# ECG_MCU_Core.net
KiCad netlist of a schematic drawn in Altium Designer
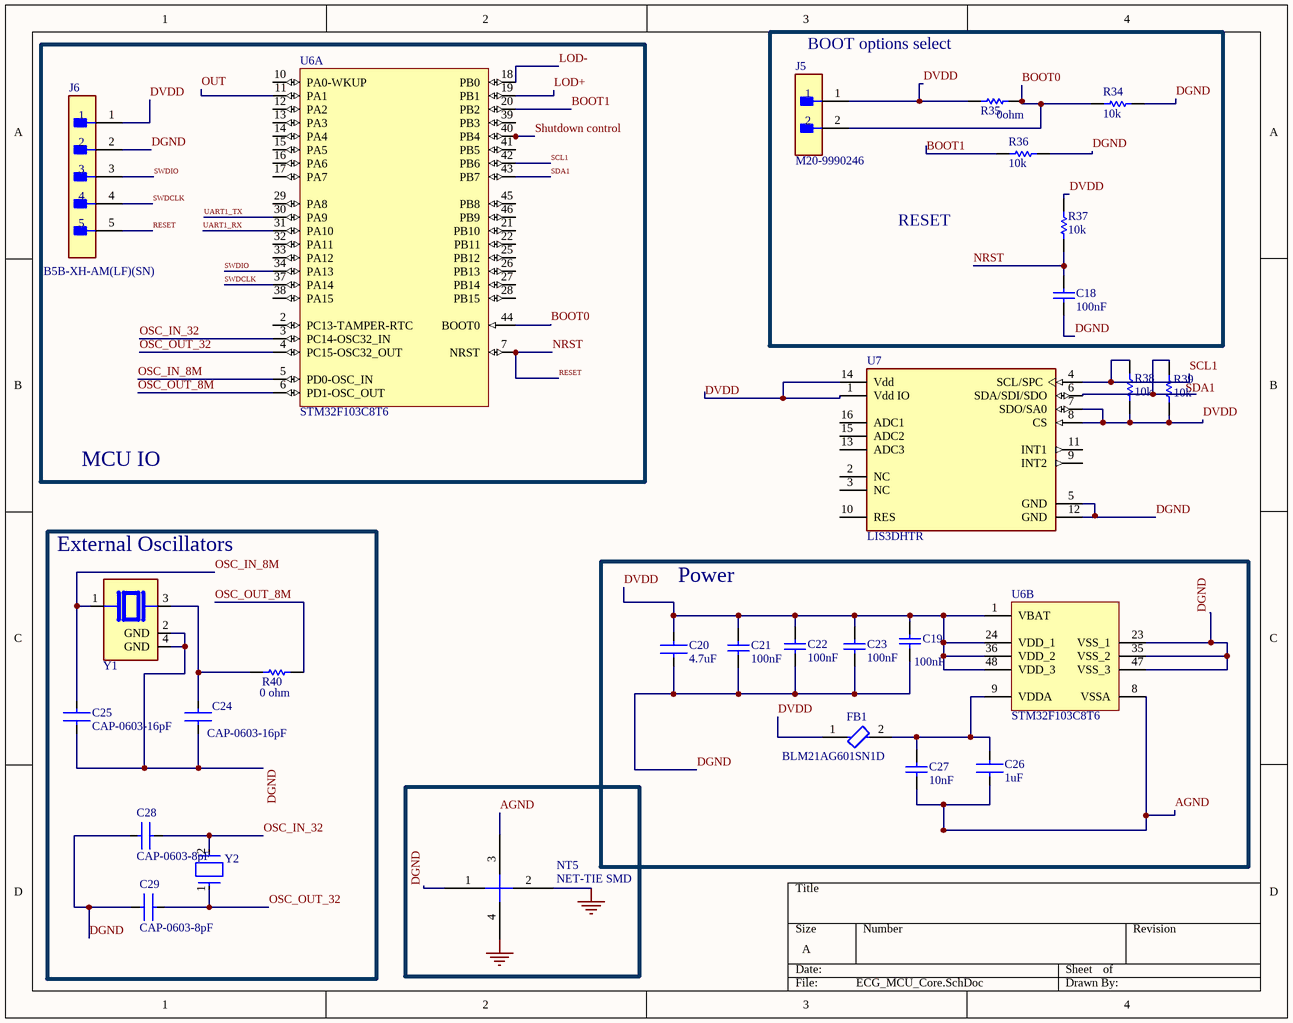
[diagram p0: ECG_MCU_Core.SchDoc]

(export (version "E")
  (design (tool "Eeschema 10.0.6"))
  (components
    (comp (ref "C18")
      (value "100nF")
      (footprint "CAP-0603-IPC_B")
      (fields
        (field (name "MANUFACTURER") "AVX Interconnect / Elco")
        (field (name "PART NUMBER") "0603ZC103MAT2A")
      )
      (libsource (lib "ecg_device_components") (part "1nF CAP-0603-IPC-B_1"))
    )
    (comp (ref "C19")
      (value "100nF")
      (footprint "CAP-0603-IPC_B")
      (fields
        (field (name "MANUFACTURER") "AVX Interconnect / Elco")
        (field (name "PART NUMBER") "0603ZC103MAT2A")
      )
      (libsource (lib "ecg_device_components") (part "CAP-0603-IPC-B"))
    )
    (comp (ref "C20")
      (value "4.7uF")
      (footprint "CAP-0805-IPC_B")
      (libsource (lib "ecg_device_components") (part "4.7uF CAP-0805-IPC-B_1"))
    )
    (comp (ref "C21")
      (value "100nF")
      (footprint "CAP-0603-IPC_B")
      (fields
        (field (name "MANUFACTURER") "AVX Interconnect / Elco")
        (field (name "PART NUMBER") "0603ZC103MAT2A")
      )
      (libsource (lib "ecg_device_components") (part "CAP-0603-IPC-B"))
    )
    (comp (ref "C22")
      (value "100nF")
      (footprint "CAP-0603-IPC_B")
      (fields
        (field (name "MANUFACTURER") "AVX Interconnect / Elco")
        (field (name "PART NUMBER") "0603ZC103MAT2A")
      )
      (libsource (lib "ecg_device_components") (part "CAP-0603-IPC-B"))
    )
    (comp (ref "C23")
      (value "100nF")
      (footprint "CAP-0603-IPC_B")
      (fields
        (field (name "MANUFACTURER") "AVX Interconnect / Elco")
        (field (name "PART NUMBER") "0603ZC103MAT2A")
      )
      (libsource (lib "ecg_device_components") (part "CAP-0603-IPC-B"))
    )
    (comp (ref "C24")
      (value "CAP-0603-16pF")
      (footprint "FP-GCM188-0_1-IPC_A_murata")
      (description "Ceramic Capacitor for Automotive 16pF  ±5% 100VDC C0G 0603 Paper T/R")
      (fields (field (name "TOLERANCE") "5%"))
      (libsource (lib "ecg_device_components") (part "CAP-0603_16V- 16pf_murata"))
    )
    (comp (ref "C25")
      (value "CAP-0603-16pF")
      (footprint "FP-GCM188-0_1-IPC_A_murata")
      (description "Ceramic Capacitor for Automotive 16pF  ±5% 100VDC C0G 0603 Paper T/R")
      (fields (field (name "TOLERANCE") "5%"))
      (libsource (lib "ecg_device_components") (part "CAP-0603_16V- 16pf_murata"))
    )
    (comp (ref "C26")
      (value "1uF")
      (footprint "CAP-0805-IPC_B")
      (libsource (lib "ecg_device_components") (part "1uF CAP-0805-IPC-B_1"))
    )
    (comp (ref "C27")
      (value "10nF")
      (footprint "CAP-0603-IPC_B")
      (fields
        (field (name "MANUFACTURER") "AVX Interconnect / Elco")
        (field (name "PART NUMBER") "0603ZC103MAT2A")
      )
      (libsource (lib "ecg_device_components") (part "CAP-0603-IPC-B"))
    )
    (comp (ref "C28")
      (value "CAP-0603-8pF")
      (footprint "FP-GCM188-0_1-IPC_A_murata")
      (description "Ceramic Capacitor for Automotive 16pF  ±5% 100VDC C0G 0603 Paper T/R")
      (fields (field (name "TOLERANCE") "5%"))
      (libsource (lib "ecg_device_components") (part "CAP-0603_16V- 8pF_murata"))
    )
    (comp (ref "C29")
      (value "CAP-0603-8pF")
      (footprint "FP-GCM188-0_1-IPC_A_murata")
      (description "Ceramic Capacitor for Automotive 16pF  ±5% 100VDC C0G 0603 Paper T/R")
      (fields (field (name "TOLERANCE") "5%"))
      (libsource (lib "ecg_device_components") (part "CAP-0603_16V- 8pF_murata"))
    )
    (comp (ref "FB1")
      (value "BLM21AG601SN1D")
      (footprint "Ferrite bead")
      (description "Chip Ferrite Bead, 0805, 600Ω @ 100MHz, 0.2Ω, 25%, 700mA")
      (fields (field (name "TOLERANCE") "25%"))
      (libsource (lib "ecg_device_components") (part "CMP-0686-00639-3 Ferrite bead"))
    )
    (comp (ref "J5")
      (value "M20-9990246")
      (footprint "FP-M20-9990246-MFG")
      (description "CONN HEADER VERT 2POS 2.54MM")
      (fields
        (field (name "OCTOPART") "https://octopart.com/m20-9990246-harwin-2590635")
        (field (name "MANUFACTURER") "Harwin")
      )
      (libsource (lib "Altium Content Vault") (part "3bc925449376181038e59eaffc5286c"))
    )
    (comp (ref "J6")
      (value "B5B-XH-AM(LF)(SN)")
      (footprint "FP-B5B-XH-AM_LF_SN-MFG")
      (description "CONN HEADER VERT 5POS 2.5MM")
      (libsource (lib "Altium Content Vault") (part "bf93c07fd2649a848d0ec8585582aab"))
    )
    (comp (ref "NT5")
      (value "NET-TIE SMD")
      (footprint "NET TIE SMD")
      (libsource (lib "ecg_device_components") (part "NET-TIE SMD"))
    )
    (comp (ref "R34")
      (value "10k")
      (footprint "RES-0603-IPC_B")
      (fields (field (name "TOLERANCE") "0.5%"))
      (libsource (lib "ecg_device_components") (part "10k RES-0603-IPC-B_1_1"))
    )
    (comp (ref "R35")
      (value "0ohm")
      (footprint "RES-0603-IPC_B")
      (fields (field (name "TOLERANCE") "0.5%"))
      (libsource (lib "ecg_device_components") (part "1k RES-0603-IPC-B_1"))
    )
    (comp (ref "R36")
      (value "10k")
      (footprint "RES-0603-IPC_B")
      (fields (field (name "TOLERANCE") "0.5%"))
      (libsource (lib "ecg_device_components") (part "10k RES-0603-IPC-B_1_1"))
    )
    (comp (ref "R37")
      (value "10k")
      (footprint "RES-0603-IPC_B")
      (fields (field (name "TOLERANCE") "0.5%"))
      (libsource (lib "ecg_device_components") (part "10k RES-0603-IPC-B_1_1"))
    )
    (comp (ref "R38")
      (value "10k")
      (footprint "RES-0603-IPC_B")
      (fields (field (name "TOLERANCE") "0.5%"))
      (libsource (lib "ecg_device_components") (part "10k RES-0603-IPC-B_1_1"))
    )
    (comp (ref "R39")
      (value "10k")
      (footprint "RES-0603-IPC_B")
      (fields (field (name "TOLERANCE") "0.5%"))
      (libsource (lib "ecg_device_components") (part "10k RES-0603-IPC-B_1_1"))
    )
    (comp (ref "R40")
      (value "0 ohm")
      (footprint "RES-0603-IPC_B")
      (fields (field (name "TOLERANCE") "0.5%"))
      (libsource (lib "ecg_device_components") (part "RES-0603-IPC-B"))
    )
    (comp (ref "U6")
      (value "STM32F103C8T6")
      (footprint "STM-LQFP48_M")
      (description "MCU 32-bit STM32F1 ARM Cortex M3 RISC 64KB Flash 2.5V/3.3V 48-Pin LQFP Tray")
      (fields (field (name "MANUFACTURER") "STMicroelectronics"))
      (libsource (lib "ecg_device_components") (part "STM32F103C8T6"))
    )
    (comp (ref "U7")
      (value "LIS3DHTR")
      (footprint "FP-LGA-16-7983231-MFG")
      (description "ACCEL 2-16G I2C/SPI 16LGA")
      (libsource (lib "Altium Content Vault") (part "1e4772b22d749da4b53766bc623c8dd"))
    )
    (comp (ref "Y1")
      (value "ABM8AIG-8.000MHZ-1Z-T_1")
      (footprint "XTAL_ABM8AIG-8.000MHZ-1Z-T")
      (description "Crystal, Aec-Q200, 8Mhz, 3.2Mm X 2.5Mm Rohs Compliant: Yes ¦Abracon ABM8AIG-8.000MHZ-1Z-T")
      (fields (field (name "MF") "Abracon LLC") (field (name "MP") "ABM8AIG-8.000MHZ-1Z-T"))
      (libsource (lib "ecg_device_components") (part "ABM8AIG-8.000MHZ-1Z-T_1"))
    )
    (comp (ref "Y2")
      (value "ABS07-32.768KHZ-6-T")
      (footprint "FP-ABS07-MFG")
      (description "Crystal 32.768kHz ±20ppm (Tol) 6pF FUND 70kΩ 2-Pin CSMD T/R")
      (fields (field (name "TOLERANCE") "20ppm"))
      (libsource (lib "Altium Content Vault") (part "c23a69dc6c9e2f18f2079038eb95dd1"))
    )
  )
  (nets
    (net (code "1") (name "/AGND") (class "Default")
      (node (ref "C26") (pin "1") (pinfunction "1_1") (pintype "passive"))
      (node (ref "C27") (pin "1") (pinfunction "1_1") (pintype "passive"))
      (node (ref "NT5") (pin "3") (pinfunction "3_3") (pintype "passive"))
      (node (ref "U6") (pin "8") (pinfunction "VSSA_8") (pintype "power_in"))
    )
    (net (code "2") (name "/BOOT0") (class "Default")
      (node (ref "J5") (pin "2") (pinfunction "2_2") (pintype "passive"))
      (node (ref "R34") (pin "1") (pinfunction "1_1") (pintype "passive"))
      (node (ref "R35") (pin "2") (pinfunction "2_2") (pintype "passive"))
      (node (ref "U6") (pin "44") (pinfunction "BOOT0_44") (pintype "input"))
    )
    (net (code "3") (name "/BOOT1") (class "Default")
      (node (ref "R36") (pin "1") (pinfunction "1_1") (pintype "passive"))
      (node (ref "U6") (pin "20") (pinfunction "PB2_20") (pintype "bidirectional"))
    )
    (net (code "4") (name "/DGND") (class "Default")
      (node (ref "C18") (pin "1") (pinfunction "1_1") (pintype "passive"))
      (node (ref "C19") (pin "1") (pinfunction "1_1") (pintype "passive"))
      (node (ref "C20") (pin "2") (pinfunction "2_2") (pintype "passive"))
      (node (ref "C21") (pin "1") (pinfunction "1_1") (pintype "passive"))
      (node (ref "C22") (pin "1") (pinfunction "1_1") (pintype "passive"))
      (node (ref "C23") (pin "1") (pinfunction "1_1") (pintype "passive"))
      (node (ref "C24") (pin "1") (pinfunction "1_1") (pintype "passive"))
      (node (ref "C25") (pin "1") (pinfunction "1_1") (pintype "passive"))
      (node (ref "C28") (pin "2") (pinfunction "2_2") (pintype "passive"))
      (node (ref "C29") (pin "1") (pinfunction "1_1") (pintype "passive"))
      (node (ref "J6") (pin "2") (pinfunction "2_2") (pintype "passive"))
      (node (ref "NT5") (pin "1") (pinfunction "0_1") (pintype "passive"))
      (node (ref "R34") (pin "2") (pinfunction "2_2") (pintype "passive"))
      (node (ref "R36") (pin "2") (pinfunction "2_2") (pintype "passive"))
      (node (ref "U6") (pin "23") (pinfunction "VSS_1_23") (pintype "power_in"))
      (node (ref "U6") (pin "35") (pinfunction "VSS_2_35") (pintype "power_in"))
      (node (ref "U6") (pin "47") (pinfunction "VSS_3_47") (pintype "power_in"))
      (node (ref "U7") (pin "12") (pinfunction "GND_12") (pintype "power_in"))
      (node (ref "U7") (pin "5") (pinfunction "GND_5") (pintype "power_in"))
      (node (ref "Y1") (pin "2") (pinfunction "GND_2") (pintype "power_in"))
      (node (ref "Y1") (pin "4") (pinfunction "GND_4") (pintype "power_in"))
    )
    (net (code "5") (name "/DVDD") (class "Default")
      (node (ref "C19") (pin "2") (pinfunction "2_2") (pintype "passive"))
      (node (ref "C20") (pin "1") (pinfunction "1_1") (pintype "passive"))
      (node (ref "C21") (pin "2") (pinfunction "2_2") (pintype "passive"))
      (node (ref "C22") (pin "2") (pinfunction "2_2") (pintype "passive"))
      (node (ref "C23") (pin "2") (pinfunction "2_2") (pintype "passive"))
      (node (ref "FB1") (pin "1") (pinfunction "1_1") (pintype "passive"))
      (node (ref "J5") (pin "1") (pinfunction "1_1") (pintype "passive"))
      (node (ref "J6") (pin "1") (pinfunction "1_1") (pintype "passive"))
      (node (ref "R35") (pin "1") (pinfunction "1_1") (pintype "passive"))
      (node (ref "R37") (pin "2") (pinfunction "2_2") (pintype "passive"))
      (node (ref "R38") (pin "1") (pinfunction "1_1") (pintype "passive"))
      (node (ref "R39") (pin "1") (pinfunction "1_1") (pintype "passive"))
      (node (ref "U6") (pin "1") (pinfunction "VBAT_1") (pintype "power_in"))
      (node (ref "U6") (pin "24") (pinfunction "VDD_1_24") (pintype "power_in"))
      (node (ref "U6") (pin "36") (pinfunction "VDD_2_36") (pintype "power_in"))
      (node (ref "U6") (pin "48") (pinfunction "VDD_3_48") (pintype "power_in"))
      (node (ref "U7") (pin "1") (pinfunction "Vdd_IO_1") (pintype "power_in"))
      (node (ref "U7") (pin "14") (pinfunction "Vdd_14") (pintype "power_in"))
      (node (ref "U7") (pin "7") (pinfunction "SDO/SA0_7") (pintype "bidirectional"))
      (node (ref "U7") (pin "8") (pinfunction "CS_8") (pintype "input"))
    )
    (net (code "6") (name "/LOD+") (class "Default")
      (node (ref "U6") (pin "19") (pinfunction "PB1_19") (pintype "bidirectional"))
    )
    (net (code "7") (name "/LOD-") (class "Default")
      (node (ref "U6") (pin "18") (pinfunction "PB0_18") (pintype "bidirectional"))
    )
    (net (code "8") (name "/NRST") (class "Default")
      (node (ref "C18") (pin "2") (pinfunction "2_2") (pintype "passive"))
      (node (ref "J6") (pin "5") (pinfunction "5_5") (pintype "passive"))
      (node (ref "R37") (pin "1") (pinfunction "1_1") (pintype "passive"))
      (node (ref "U6") (pin "7") (pinfunction "NRST_7") (pintype "bidirectional"))
    )
    (net (code "9") (name "/OSC_IN_8M") (class "Default")
      (node (ref "C25") (pin "2") (pinfunction "2_2") (pintype "passive"))
      (node (ref "U6") (pin "5") (pinfunction "PD0-OSC_IN_5") (pintype "bidirectional"))
      (node (ref "Y1") (pin "1") (pinfunction "1_1") (pintype "passive"))
    )
    (net (code "10") (name "/OSC_IN_32") (class "Default")
      (node (ref "C28") (pin "1") (pinfunction "1_1") (pintype "passive"))
      (node (ref "U6") (pin "3") (pinfunction "PC14-OSC32_IN_3") (pintype "bidirectional"))
      (node (ref "Y2") (pin "2") (pinfunction "2_2") (pintype "passive"))
    )
    (net (code "11") (name "/OSC_OUT_8M") (class "Default")
      (node (ref "R40") (pin "2") (pinfunction "2_2") (pintype "passive"))
      (node (ref "U6") (pin "6") (pinfunction "PD1-OSC_OUT_6") (pintype "bidirectional"))
    )
    (net (code "12") (name "/OSC_OUT_32") (class "Default")
      (node (ref "C29") (pin "2") (pinfunction "2_2") (pintype "passive"))
      (node (ref "U6") (pin "4") (pinfunction "PC15-OSC32_OUT_4") (pintype "bidirectional"))
      (node (ref "Y2") (pin "1") (pinfunction "1_1") (pintype "passive"))
    )
    (net (code "13") (name "/OUT") (class "Default")
      (node (ref "U6") (pin "11") (pinfunction "PA1_11") (pintype "bidirectional"))
    )
    (net (code "14") (name "/SCL1") (class "Default")
      (node (ref "R38") (pin "2") (pinfunction "2_2") (pintype "passive"))
      (node (ref "U6") (pin "42") (pinfunction "PB6_42") (pintype "bidirectional"))
      (node (ref "U7") (pin "4") (pinfunction "SCL/SPC_4") (pintype "input"))
    )
    (net (code "15") (name "/SDA1") (class "Default")
      (node (ref "U6") (pin "43") (pinfunction "PB7_43") (pintype "bidirectional"))
    )
    (net (code "16") (name "/SWDCLK") (class "Default")
      (node (ref "J6") (pin "4") (pinfunction "4_4") (pintype "passive"))
      (node (ref "U6") (pin "37") (pinfunction "PA14_37") (pintype "bidirectional"))
    )
    (net (code "17") (name "/SWDIO") (class "Default")
      (node (ref "J6") (pin "3") (pinfunction "3_3") (pintype "passive"))
      (node (ref "U6") (pin "34") (pinfunction "PA13_34") (pintype "bidirectional"))
    )
    (net (code "18") (name "/Shutdown control") (class "Default")
      (node (ref "U6") (pin "40") (pinfunction "PB4_40") (pintype "bidirectional"))
    )
    (net (code "19") (name "/UART1_RX") (class "Default")
      (node (ref "U6") (pin "31") (pinfunction "PA10_31") (pintype "bidirectional"))
    )
    (net (code "20") (name "/UART1_TX") (class "Default")
      (node (ref "U6") (pin "30") (pinfunction "PA9_30") (pintype "bidirectional"))
    )
    (net (code "21") (name "GND") (class "Default")
      (node (ref "NT5") (pin "2") (pinfunction "1_2") (pintype "passive"))
    )
    (net (code "22") (name "Net-(U6B-VDDA)") (class "Default")
      (node (ref "C26") (pin "2") (pinfunction "2_2") (pintype "passive"))
      (node (ref "C27") (pin "2") (pinfunction "2_2") (pintype "passive"))
      (node (ref "FB1") (pin "2") (pinfunction "2_2") (pintype "passive"))
      (node (ref "U6") (pin "9") (pinfunction "VDDA_9") (pintype "power_in"))
    )
    (net (code "23") (name "Net-(U7-SDA{slash}SDI{slash}SDO)") (class "Default")
      (node (ref "R39") (pin "2") (pinfunction "2_2") (pintype "passive"))
      (node (ref "U7") (pin "6") (pinfunction "SDA/SDI/SDO_6") (pintype "bidirectional"))
    )
    (net (code "24") (name "Net-(Y1-2)") (class "Default")
      (node (ref "C24") (pin "2") (pinfunction "2_2") (pintype "passive"))
      (node (ref "R40") (pin "1") (pinfunction "1_1") (pintype "passive"))
      (node (ref "Y1") (pin "3") (pinfunction "2_3") (pintype "passive"))
    )
    (net (code "25") (name "unconnected-(NT5-Pad4)") (class "Default")
      (node (ref "NT5") (pin "4") (pinfunction "4_4") (pintype "passive"))
    )
    (net (code "26") (name "unconnected-(U6A-PA0-WKUP-Pad10)") (class "Default")
      (node (ref "U6") (pin "10") (pinfunction "PA0-WKUP_10") (pintype "bidirectional"))
    )
    (net (code "27") (name "unconnected-(U6A-PA2-Pad12)") (class "Default")
      (node (ref "U6") (pin "12") (pinfunction "PA2_12") (pintype "bidirectional"))
    )
    (net (code "28") (name "unconnected-(U6A-PA3-Pad13)") (class "Default")
      (node (ref "U6") (pin "13") (pinfunction "PA3_13") (pintype "bidirectional"))
    )
    (net (code "29") (name "unconnected-(U6A-PA4-Pad14)") (class "Default")
      (node (ref "U6") (pin "14") (pinfunction "PA4_14") (pintype "bidirectional"))
    )
    (net (code "30") (name "unconnected-(U6A-PA5-Pad15)") (class "Default")
      (node (ref "U6") (pin "15") (pinfunction "PA5_15") (pintype "bidirectional"))
    )
    (net (code "31") (name "unconnected-(U6A-PA6-Pad16)") (class "Default")
      (node (ref "U6") (pin "16") (pinfunction "PA6_16") (pintype "bidirectional"))
    )
    (net (code "32") (name "unconnected-(U6A-PA7-Pad17)") (class "Default")
      (node (ref "U6") (pin "17") (pinfunction "PA7_17") (pintype "bidirectional"))
    )
    (net (code "33") (name "unconnected-(U6A-PA8-Pad29)") (class "Default")
      (node (ref "U6") (pin "29") (pinfunction "PA8_29") (pintype "bidirectional"))
    )
    (net (code "34") (name "unconnected-(U6A-PA11-Pad32)") (class "Default")
      (node (ref "U6") (pin "32") (pinfunction "PA11_32") (pintype "bidirectional"))
    )
    (net (code "35") (name "unconnected-(U6A-PA12-Pad33)") (class "Default")
      (node (ref "U6") (pin "33") (pinfunction "PA12_33") (pintype "bidirectional"))
    )
    (net (code "36") (name "unconnected-(U6A-PA15-Pad38)") (class "Default")
      (node (ref "U6") (pin "38") (pinfunction "PA15_38") (pintype "bidirectional"))
    )
    (net (code "37") (name "unconnected-(U6A-PB3-Pad39)") (class "Default")
      (node (ref "U6") (pin "39") (pinfunction "PB3_39") (pintype "bidirectional"))
    )
    (net (code "38") (name "unconnected-(U6A-PB5-Pad41)") (class "Default")
      (node (ref "U6") (pin "41") (pinfunction "PB5_41") (pintype "bidirectional"))
    )
    (net (code "39") (name "unconnected-(U6A-PB8-Pad45)") (class "Default")
      (node (ref "U6") (pin "45") (pinfunction "PB8_45") (pintype "bidirectional"))
    )
    (net (code "40") (name "unconnected-(U6A-PB9-Pad46)") (class "Default")
      (node (ref "U6") (pin "46") (pinfunction "PB9_46") (pintype "bidirectional"))
    )
    (net (code "41") (name "unconnected-(U6A-PB10-Pad21)") (class "Default")
      (node (ref "U6") (pin "21") (pinfunction "PB10_21") (pintype "bidirectional"))
    )
    (net (code "42") (name "unconnected-(U6A-PB11-Pad22)") (class "Default")
      (node (ref "U6") (pin "22") (pinfunction "PB11_22") (pintype "bidirectional"))
    )
    (net (code "43") (name "unconnected-(U6A-PB12-Pad25)") (class "Default")
      (node (ref "U6") (pin "25") (pinfunction "PB12_25") (pintype "bidirectional"))
    )
    (net (code "44") (name "unconnected-(U6A-PB13-Pad26)") (class "Default")
      (node (ref "U6") (pin "26") (pinfunction "PB13_26") (pintype "bidirectional"))
    )
    (net (code "45") (name "unconnected-(U6A-PB14-Pad27)") (class "Default")
      (node (ref "U6") (pin "27") (pinfunction "PB14_27") (pintype "bidirectional"))
    )
    (net (code "46") (name "unconnected-(U6A-PB15-Pad28)") (class "Default")
      (node (ref "U6") (pin "28") (pinfunction "PB15_28") (pintype "bidirectional"))
    )
    (net (code "47") (name "unconnected-(U6A-PC13-TAMPER-RTC-Pad2)") (class "Default")
      (node (ref "U6") (pin "2") (pinfunction "PC13-TAMPER-RTC_2") (pintype "bidirectional"))
    )
    (net (code "48") (name "unconnected-(U7-ADC1-Pad16)") (class "Default")
      (node (ref "U7") (pin "16") (pinfunction "ADC1_16") (pintype "passive"))
    )
    (net (code "49") (name "unconnected-(U7-ADC2-Pad15)") (class "Default")
      (node (ref "U7") (pin "15") (pinfunction "ADC2_15") (pintype "passive"))
    )
    (net (code "50") (name "unconnected-(U7-ADC3-Pad13)") (class "Default")
      (node (ref "U7") (pin "13") (pinfunction "ADC3_13") (pintype "passive"))
    )
    (net (code "51") (name "unconnected-(U7-INT1-Pad11)") (class "Default")
      (node (ref "U7") (pin "11") (pinfunction "INT1_11") (pintype "output"))
    )
    (net (code "52") (name "unconnected-(U7-INT2-Pad9)") (class "Default")
      (node (ref "U7") (pin "9") (pinfunction "INT2_9") (pintype "output"))
    )
    (net (code "53") (name "unconnected-(U7-NC-Pad2)") (class "Default")
      (node (ref "U7") (pin "2") (pinfunction "NC_2") (pintype "passive"))
    )
    (net (code "54") (name "unconnected-(U7-NC-Pad3)") (class "Default")
      (node (ref "U7") (pin "3") (pinfunction "NC_3") (pintype "passive"))
    )
    (net (code "55") (name "unconnected-(U7-RES-Pad10)") (class "Default")
      (node (ref "U7") (pin "10") (pinfunction "RES_10") (pintype "passive"))
    )
  )
)
